# Common_Mode_Filter.net
KiCad netlist of a schematic drawn in Altium Designer
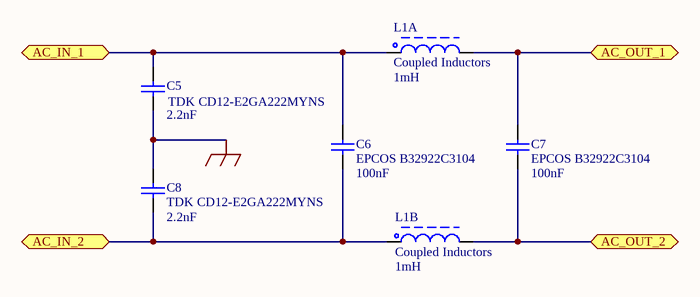
[diagram p0: Common_Mode_Filter.SchDoc]

(export (version "E")
  (design (tool "Eeschema 10.0.6"))
  (components
    (comp (ref "C5")
      (value "TDK CD12-E2GA222MYNS")
      (footprint "SAFETY Y1 type")
      (description "Safety Standard Certified Ceramic Y1 2.2nF 250Vac")
      (fields (field (name "ALTIUM_VALUE") "2.2nF") (field (name "PUBLISHER") "Altium Limited"))
      (libsource (lib "Capacitor") (part "TDK CD12-E2GA222MYNS"))
    )
    (comp (ref "C6")
      (value "EPCOS B32922C3104")
      (footprint "MKP PITCH:15mm SIZE:5mmx18mm")
      (description "MKP EMI suppression X2 100nF 305Vac")
      (fields (field (name "ALTIUM_VALUE") "100nF") (field (name "PUBLISHER") "Altium Limited"))
      (libsource (lib "Capacitor") (part "EPCOS B32922C3104"))
    )
    (comp (ref "C7")
      (value "EPCOS B32922C3104")
      (footprint "MKP PITCH:15mm SIZE:5mmx18mm")
      (description "MKP EMI suppression X2 100nF 305Vac")
      (fields (field (name "ALTIUM_VALUE") "100nF") (field (name "PUBLISHER") "Altium Limited"))
      (libsource (lib "Capacitor") (part "EPCOS B32922C3104"))
    )
    (comp (ref "C8")
      (value "TDK CD12-E2GA222MYNS")
      (footprint "SAFETY Y1 type")
      (description "Safety Standard Certified Ceramic Y1 2.2nF 250Vac")
      (fields (field (name "ALTIUM_VALUE") "2.2nF") (field (name "PUBLISHER") "Altium Limited"))
      (libsource (lib "Capacitor") (part "TDK CD12-E2GA222MYNS"))
    )
    (comp (ref "L1")
      (value "Coupled Inductors")
      (footprint "Bourns 8108-RC")
      (description "Bourns Common mode inductor 10A 1mH 8108-RC")
      (fields (field (name "ALTIUM_VALUE") "1mH") (field (name "PUBLISHER") "Altium Limited"))
      (libsource (lib "Inductor") (part "Common mode filter 10A"))
    )
  )
  (nets
    (net (code "1") (name "/AC_IN_1") (class "Default")
      (node (ref "C5") (pin "2") (pinfunction "2_2") (pintype "passive"))
      (node (ref "C6") (pin "2") (pinfunction "2_2") (pintype "passive"))
      (node (ref "L1") (pin "1") (pinfunction "1_1") (pintype "passive"))
    )
    (net (code "2") (name "/AC_IN_2") (class "Default")
      (node (ref "C6") (pin "1") (pinfunction "1_1") (pintype "passive"))
      (node (ref "C8") (pin "2") (pinfunction "2_2") (pintype "passive"))
      (node (ref "L1") (pin "4") (pinfunction "4_4") (pintype "passive"))
    )
    (net (code "3") (name "/AC_OUT_1") (class "Default")
      (node (ref "C7") (pin "2") (pinfunction "2_2") (pintype "passive"))
      (node (ref "L1") (pin "2") (pinfunction "2_2") (pintype "passive"))
    )
    (net (code "4") (name "/AC_OUT_2") (class "Default")
      (node (ref "C7") (pin "1") (pinfunction "1_1") (pintype "passive"))
      (node (ref "L1") (pin "3") (pinfunction "3_3") (pintype "passive"))
    )
    (net (code "5") (name "EARTH") (class "Default")
      (node (ref "C5") (pin "1") (pinfunction "1_1") (pintype "passive"))
      (node (ref "C8") (pin "1") (pinfunction "1_1") (pintype "passive"))
    )
  )
)
